# 4-20mA_Sensor.net
KiCad netlist of a schematic drawn in Altium Designer
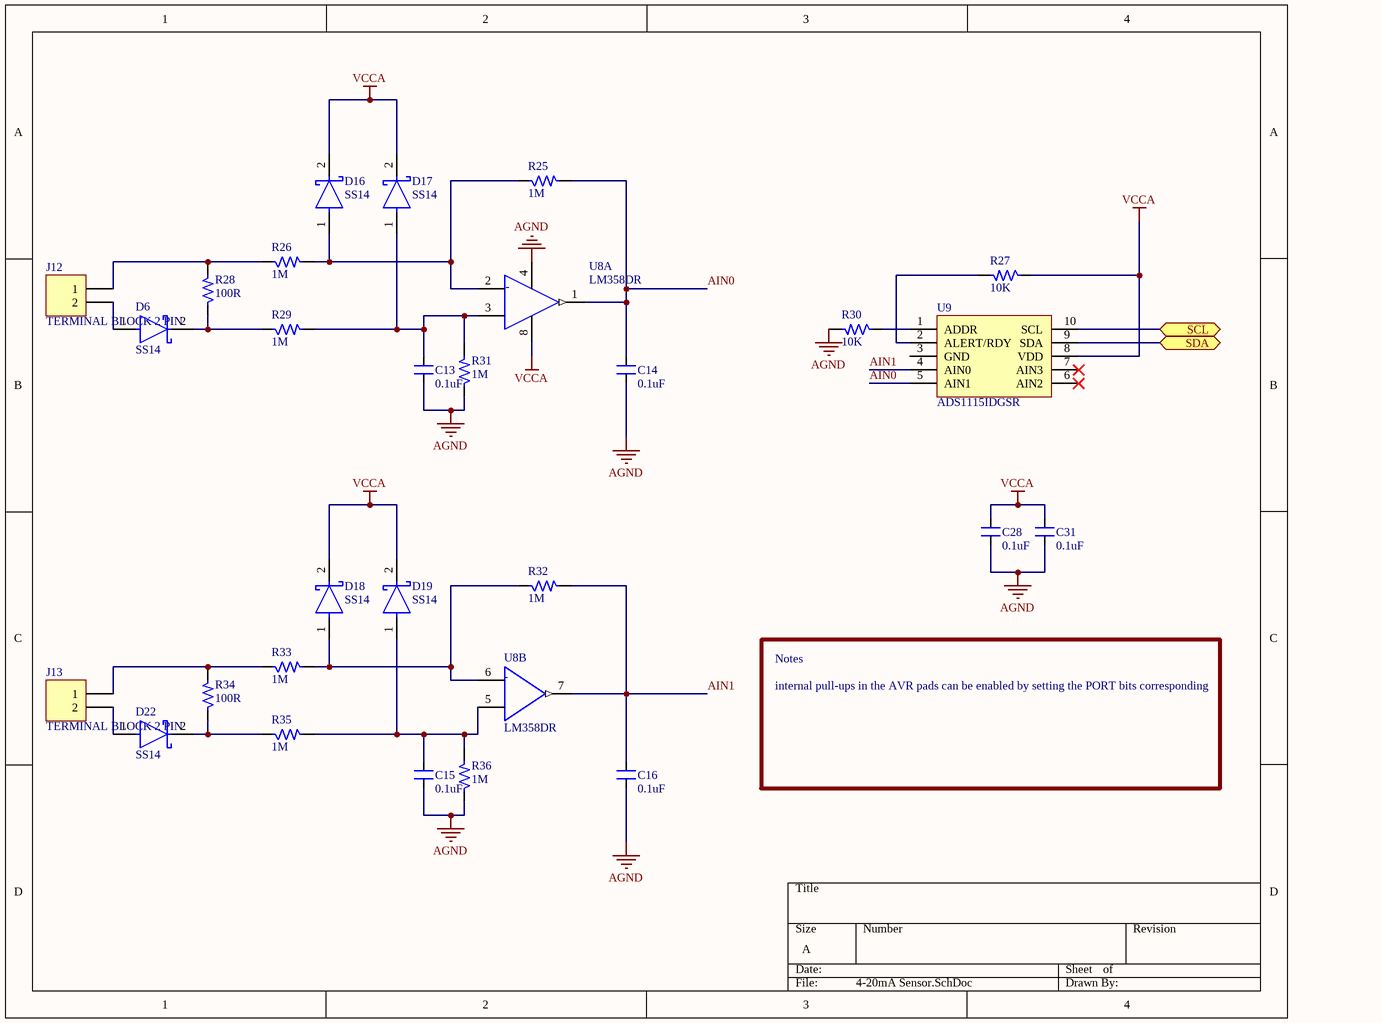
[diagram p0: 4-20mA Sensor.SchDoc]

(export (version "E")
  (design (tool "Eeschema 10.0.6"))
  (components
    (comp (ref "C13")
      (value "0.1uF")
      (footprint "CAP_0805")
      (description "0.1µF ±5% 50V Ceramic Capacitor X7R 0805 (2012 Metric)")
      (fields
        (field (name "MANUFACTURER") "AVX Corporation")
        (field (name "MANUFACTURER PART NUMBER") "08055C104JAT4A")
      )
      (libsource (lib "ESTEEMPCBLIB") (part "CAP_0.1uF-50V-5%-0805"))
    )
    (comp (ref "C14")
      (value "0.1uF")
      (footprint "CAP_0805")
      (description "0.1µF ±5% 50V Ceramic Capacitor X7R 0805 (2012 Metric)")
      (fields
        (field (name "MANUFACTURER") "AVX Corporation")
        (field (name "MANUFACTURER PART NUMBER") "08055C104JAT4A")
      )
      (libsource (lib "ESTEEMPCBLIB") (part "CAP_0.1uF-50V-5%-0805"))
    )
    (comp (ref "C15")
      (value "0.1uF")
      (footprint "CAP_0805")
      (description "0.1µF ±5% 50V Ceramic Capacitor X7R 0805 (2012 Metric)")
      (fields
        (field (name "MANUFACTURER") "AVX Corporation")
        (field (name "MANUFACTURER PART NUMBER") "08055C104JAT4A")
      )
      (libsource (lib "ESTEEMPCBLIB") (part "CAP_0.1uF-50V-5%-0805"))
    )
    (comp (ref "C16")
      (value "0.1uF")
      (footprint "CAP_0805")
      (description "0.1µF ±5% 50V Ceramic Capacitor X7R 0805 (2012 Metric)")
      (fields
        (field (name "MANUFACTURER") "AVX Corporation")
        (field (name "MANUFACTURER PART NUMBER") "08055C104JAT4A")
      )
      (libsource (lib "ESTEEMPCBLIB") (part "CAP_0.1uF-50V-5%-0805"))
    )
    (comp (ref "C28")
      (value "0.1uF")
      (footprint "CAP_0805")
      (description "0.1µF ±5% 50V Ceramic Capacitor X7R 0805 (2012 Metric)")
      (fields
        (field (name "MANUFACTURER") "AVX Corporation")
        (field (name "MANUFACTURER PART NUMBER") "08055C104JAT4A")
      )
      (libsource (lib "ESTEEMPCBLIB") (part "CAP_0.1uF-50V-5%-0805"))
    )
    (comp (ref "C31")
      (value "0.1uF")
      (footprint "CAP_0805")
      (description "0.1µF ±5% 50V Ceramic Capacitor X7R 0805 (2012 Metric)")
      (fields
        (field (name "MANUFACTURER") "AVX Corporation")
        (field (name "MANUFACTURER PART NUMBER") "08055C104JAT4A")
      )
      (libsource (lib "ESTEEMPCBLIB") (part "CAP_0.1uF-50V-5%-0805"))
    )
    (comp (ref "D6")
      (value "SS14")
      (footprint "FP-403AE-MFG")
      (description "DIODE SCHOTTKY 40V 1A SMA")
      (fields
        (field (name "MANUFACTURER") "ON Semiconductor")
        (field (name "OCTOPART") "https://octopart.com/ss14-on+semiconductor-29205033")
      )
      (libsource (lib "TAREKPCBLIB") (part "SS14"))
    )
    (comp (ref "D16")
      (value "SS14")
      (footprint "FP-403AE-MFG")
      (description "DIODE SCHOTTKY 40V 1A SMA")
      (fields
        (field (name "MANUFACTURER") "ON Semiconductor")
        (field (name "OCTOPART") "https://octopart.com/ss14-on+semiconductor-29205033")
      )
      (libsource (lib "TAREKPCBLIB") (part "SS14"))
    )
    (comp (ref "D17")
      (value "SS14")
      (footprint "FP-403AE-MFG")
      (description "DIODE SCHOTTKY 40V 1A SMA")
      (fields
        (field (name "MANUFACTURER") "ON Semiconductor")
        (field (name "OCTOPART") "https://octopart.com/ss14-on+semiconductor-29205033")
      )
      (libsource (lib "TAREKPCBLIB") (part "SS14"))
    )
    (comp (ref "D18")
      (value "SS14")
      (footprint "FP-403AE-MFG")
      (description "DIODE SCHOTTKY 40V 1A SMA")
      (fields
        (field (name "MANUFACTURER") "ON Semiconductor")
        (field (name "OCTOPART") "https://octopart.com/ss14-on+semiconductor-29205033")
      )
      (libsource (lib "TAREKPCBLIB") (part "SS14"))
    )
    (comp (ref "D19")
      (value "SS14")
      (footprint "FP-403AE-MFG")
      (description "DIODE SCHOTTKY 40V 1A SMA")
      (fields
        (field (name "MANUFACTURER") "ON Semiconductor")
        (field (name "OCTOPART") "https://octopart.com/ss14-on+semiconductor-29205033")
      )
      (libsource (lib "TAREKPCBLIB") (part "SS14"))
    )
    (comp (ref "D22")
      (value "SS14")
      (footprint "FP-403AE-MFG")
      (description "DIODE SCHOTTKY 40V 1A SMA")
      (fields
        (field (name "MANUFACTURER") "ON Semiconductor")
        (field (name "OCTOPART") "https://octopart.com/ss14-on+semiconductor-29205033")
      )
      (libsource (lib "TAREKPCBLIB") (part "SS14"))
    )
    (comp (ref "J12")
      (value "TERMINAL BLOCK 2 PIN")
      (footprint "CON2_P196_1729128_TH_ST")
      (description "2 Pins, 1 Row 5mm Pitch, straight Connector, male")
      (fields
        (field (name "MANUFACTURER") "Phoenix Contact")
        (field (name "MANUFACTURER PART NUMBER") "MKDSN1,5/2")
      )
      (libsource (lib "ESTEEMPCBLIB") (part "CON-TB_2X1-196-ST-TH"))
    )
    (comp (ref "J13")
      (value "TERMINAL BLOCK 2 PIN")
      (footprint "CON2_P196_1729128_TH_ST")
      (description "2 Pins, 1 Row 5mm Pitch, straight Connector, male")
      (fields
        (field (name "MANUFACTURER") "Phoenix Contact")
        (field (name "MANUFACTURER PART NUMBER") "MKDSN1,5/2")
      )
      (libsource (lib "ESTEEMPCBLIB") (part "CON-TB_2X1-196-ST-TH"))
    )
    (comp (ref "R25")
      (value "1M")
      (footprint "RES_0805")
      (description "1 MOhms ±1% 0.125W, 1/8W Chip Resistor 0805 (2012 Metric) Automotive AEC-Q200 Thick Film")
      (fields (field (name "MANUFACTURER") "Walsin") (field (name "MANUFACTURER PART NUMBER") "WR08X1004FTL"))
      (libsource (lib "ESTEEMPCBLIB") (part "RES_1M-0.125W-1%-0805"))
    )
    (comp (ref "R26")
      (value "1M")
      (footprint "RES_0805")
      (description "1 MOhms ±1% 0.125W, 1/8W Chip Resistor 0805 (2012 Metric) Automotive AEC-Q200 Thick Film")
      (fields (field (name "MANUFACTURER") "Walsin") (field (name "MANUFACTURER PART NUMBER") "WR08X1004FTL"))
      (libsource (lib "ESTEEMPCBLIB") (part "RES_1M-0.125W-1%-0805"))
    )
    (comp (ref "R27")
      (value "10K")
      (footprint "RES_0805")
      (description "10 kOhms ±1% 0.125W, 1/8W Chip Resistor 0805 (2012 Metric) Automotive AEC-Q200 Thick Film")
      (fields (field (name "MANUFACTURER") "CTS") (field (name "MANUFACTURER PART NUMBER") "WR08X1002FTL"))
      (libsource (lib "ESTEEMPCBLIB") (part "RES_10K-0.125W-1%-0805"))
    )
    (comp (ref "R28")
      (value "100R")
      (footprint "RES_0805")
      (fields (field (name "MANUFACTURER") "Walsin") (field (name "MANUFACTURER PART NUMBER") "WR08X1000FTL"))
      (libsource (lib "ESTEEMPCBLIB") (part "RES_100R-0.125W-1%-0805"))
    )
    (comp (ref "R29")
      (value "1M")
      (footprint "RES_0805")
      (description "1 MOhms ±1% 0.125W, 1/8W Chip Resistor 0805 (2012 Metric) Automotive AEC-Q200 Thick Film")
      (fields (field (name "MANUFACTURER") "Walsin") (field (name "MANUFACTURER PART NUMBER") "WR08X1004FTL"))
      (libsource (lib "ESTEEMPCBLIB") (part "RES_1M-0.125W-1%-0805"))
    )
    (comp (ref "R30")
      (value "10K")
      (footprint "RES_0805")
      (description "10 kOhms ±1% 0.125W, 1/8W Chip Resistor 0805 (2012 Metric) Automotive AEC-Q200 Thick Film")
      (fields (field (name "MANUFACTURER") "CTS") (field (name "MANUFACTURER PART NUMBER") "WR08X1002FTL"))
      (libsource (lib "ESTEEMPCBLIB") (part "RES_10K-0.125W-1%-0805"))
    )
    (comp (ref "R31")
      (value "1M")
      (footprint "RES_0805")
      (description "1 MOhms ±1% 0.125W, 1/8W Chip Resistor 0805 (2012 Metric) Automotive AEC-Q200 Thick Film")
      (fields (field (name "MANUFACTURER") "Walsin") (field (name "MANUFACTURER PART NUMBER") "WR08X1004FTL"))
      (libsource (lib "ESTEEMPCBLIB") (part "RES_1M-0.125W-1%-0805"))
    )
    (comp (ref "R32")
      (value "1M")
      (footprint "RES_0805")
      (description "1 MOhms ±1% 0.125W, 1/8W Chip Resistor 0805 (2012 Metric) Automotive AEC-Q200 Thick Film")
      (fields (field (name "MANUFACTURER") "Walsin") (field (name "MANUFACTURER PART NUMBER") "WR08X1004FTL"))
      (libsource (lib "ESTEEMPCBLIB") (part "RES_1M-0.125W-1%-0805"))
    )
    (comp (ref "R33")
      (value "1M")
      (footprint "RES_0805")
      (description "1 MOhms ±1% 0.125W, 1/8W Chip Resistor 0805 (2012 Metric) Automotive AEC-Q200 Thick Film")
      (fields (field (name "MANUFACTURER") "Walsin") (field (name "MANUFACTURER PART NUMBER") "WR08X1004FTL"))
      (libsource (lib "ESTEEMPCBLIB") (part "RES_1M-0.125W-1%-0805"))
    )
    (comp (ref "R34")
      (value "100R")
      (footprint "RES_0805")
      (fields (field (name "MANUFACTURER") "Walsin") (field (name "MANUFACTURER PART NUMBER") "WR08X1000FTL"))
      (libsource (lib "ESTEEMPCBLIB") (part "RES_100R-0.125W-1%-0805"))
    )
    (comp (ref "R35")
      (value "1M")
      (footprint "RES_0805")
      (description "1 MOhms ±1% 0.125W, 1/8W Chip Resistor 0805 (2012 Metric) Automotive AEC-Q200 Thick Film")
      (fields (field (name "MANUFACTURER") "Walsin") (field (name "MANUFACTURER PART NUMBER") "WR08X1004FTL"))
      (libsource (lib "ESTEEMPCBLIB") (part "RES_1M-0.125W-1%-0805"))
    )
    (comp (ref "R36")
      (value "1M")
      (footprint "RES_0805")
      (description "1 MOhms ±1% 0.125W, 1/8W Chip Resistor 0805 (2012 Metric) Automotive AEC-Q200 Thick Film")
      (fields (field (name "MANUFACTURER") "Walsin") (field (name "MANUFACTURER PART NUMBER") "WR08X1004FTL"))
      (libsource (lib "ESTEEMPCBLIB") (part "RES_1M-0.125W-1%-0805"))
    )
    (comp (ref "U8")
      (value "LM358DR")
      (footprint "FP-D0008A-IPC_B")
      (description "IC OPAMP GP 2 CIRCUIT 8SOIC")
      (libsource (lib "TAREKPCBLIB") (part "LM358"))
    )
    (comp (ref "U9")
      (value "ADS1115IDGSR")
      (footprint "VSOP-10_19.6_230_57X12_SMD")
      (description "Analog to Digital Converters - ADC 16B ADC w/ Int MUX PGA Comp Osc & Ref")
      (fields (field (name "MANUFACTURER") "Texas Instruments"))
      (libsource (lib "ESTEEMPCBLIB") (part "IC_ADS1115IDGSR"))
    )
  )
  (nets
    (net (code "1") (name "/AIN0") (class "Default")
      (node (ref "C14") (pin "2") (pinfunction "2_2") (pintype "passive"))
      (node (ref "R25") (pin "2") (pinfunction "2_2") (pintype "passive"))
      (node (ref "U8") (pin "1") (pinfunction "1OUT_1") (pintype "output"))
      (node (ref "U9") (pin "5") (pinfunction "AIN1_5") (pintype "passive"))
    )
    (net (code "2") (name "/AIN1") (class "Default")
      (node (ref "C16") (pin "2") (pinfunction "2_2") (pintype "passive"))
      (node (ref "R32") (pin "2") (pinfunction "2_2") (pintype "passive"))
      (node (ref "U8") (pin "7") (pinfunction "2OUT_7") (pintype "output"))
      (node (ref "U9") (pin "4") (pinfunction "AIN0_4") (pintype "passive"))
    )
    (net (code "3") (name "/SCL") (class "Default")
      (node (ref "U9") (pin "10") (pinfunction "SCL_10") (pintype "passive"))
    )
    (net (code "4") (name "/SDA") (class "Default")
      (node (ref "U9") (pin "9") (pinfunction "SDA_9") (pintype "passive"))
    )
    (net (code "5") (name "AGND") (class "Default")
      (node (ref "C13") (pin "1") (pinfunction "1_1") (pintype "passive"))
      (node (ref "C14") (pin "1") (pinfunction "1_1") (pintype "passive"))
      (node (ref "C15") (pin "1") (pinfunction "1_1") (pintype "passive"))
      (node (ref "C16") (pin "1") (pinfunction "1_1") (pintype "passive"))
      (node (ref "C28") (pin "1") (pinfunction "1_1") (pintype "passive"))
      (node (ref "C31") (pin "1") (pinfunction "1_1") (pintype "passive"))
      (node (ref "R30") (pin "2") (pinfunction "2_2") (pintype "passive"))
      (node (ref "R31") (pin "1") (pinfunction "1_1") (pintype "passive"))
      (node (ref "R36") (pin "1") (pinfunction "1_1") (pintype "passive"))
      (node (ref "U8") (pin "4") (pinfunction "V-_4") (pintype "power_in"))
    )
    (net (code "6") (name "Net-(D6-A)") (class "Default")
      (node (ref "D6") (pin "1") (pinfunction "A_1") (pintype "passive"))
      (node (ref "J12") (pin "2") (pinfunction "2_2") (pintype "passive"))
    )
    (net (code "7") (name "Net-(D6-C)") (class "Default")
      (node (ref "D6") (pin "2") (pinfunction "C_2") (pintype "passive"))
      (node (ref "R28") (pin "1") (pinfunction "1_1") (pintype "passive"))
      (node (ref "R29") (pin "1") (pinfunction "1_1") (pintype "passive"))
    )
    (net (code "8") (name "Net-(D16-A)") (class "Default")
      (node (ref "D16") (pin "1") (pinfunction "A_1") (pintype "passive"))
      (node (ref "R25") (pin "1") (pinfunction "1_1") (pintype "passive"))
      (node (ref "R26") (pin "2") (pinfunction "2_2") (pintype "passive"))
      (node (ref "U8") (pin "2") (pinfunction "IN1-_2") (pintype "tri_state"))
    )
    (net (code "9") (name "Net-(D17-A)") (class "Default")
      (node (ref "C13") (pin "2") (pinfunction "2_2") (pintype "passive"))
      (node (ref "D17") (pin "1") (pinfunction "A_1") (pintype "passive"))
      (node (ref "R29") (pin "2") (pinfunction "2_2") (pintype "passive"))
      (node (ref "R31") (pin "2") (pinfunction "2_2") (pintype "passive"))
      (node (ref "U8") (pin "3") (pinfunction "IN1+_3") (pintype "tri_state"))
    )
    (net (code "10") (name "Net-(D18-A)") (class "Default")
      (node (ref "D18") (pin "1") (pinfunction "A_1") (pintype "passive"))
      (node (ref "R32") (pin "1") (pinfunction "1_1") (pintype "passive"))
      (node (ref "R33") (pin "2") (pinfunction "2_2") (pintype "passive"))
      (node (ref "U8") (pin "6") (pinfunction "IN2-_6") (pintype "tri_state"))
    )
    (net (code "11") (name "Net-(D19-A)") (class "Default")
      (node (ref "C15") (pin "2") (pinfunction "2_2") (pintype "passive"))
      (node (ref "D19") (pin "1") (pinfunction "A_1") (pintype "passive"))
      (node (ref "R35") (pin "2") (pinfunction "2_2") (pintype "passive"))
      (node (ref "R36") (pin "2") (pinfunction "2_2") (pintype "passive"))
      (node (ref "U8") (pin "5") (pinfunction "IN2+_5") (pintype "tri_state"))
    )
    (net (code "12") (name "Net-(D22-A)") (class "Default")
      (node (ref "D22") (pin "1") (pinfunction "A_1") (pintype "passive"))
      (node (ref "J13") (pin "2") (pinfunction "2_2") (pintype "passive"))
    )
    (net (code "13") (name "Net-(D22-C)") (class "Default")
      (node (ref "D22") (pin "2") (pinfunction "C_2") (pintype "passive"))
      (node (ref "R34") (pin "1") (pinfunction "1_1") (pintype "passive"))
      (node (ref "R35") (pin "1") (pinfunction "1_1") (pintype "passive"))
    )
    (net (code "14") (name "Net-(J12-Pad1)") (class "Default")
      (node (ref "J12") (pin "1") (pinfunction "1_1") (pintype "passive"))
      (node (ref "R26") (pin "1") (pinfunction "1_1") (pintype "passive"))
      (node (ref "R28") (pin "2") (pinfunction "2_2") (pintype "passive"))
    )
    (net (code "15") (name "Net-(J13-Pad1)") (class "Default")
      (node (ref "J13") (pin "1") (pinfunction "1_1") (pintype "passive"))
      (node (ref "R33") (pin "1") (pinfunction "1_1") (pintype "passive"))
      (node (ref "R34") (pin "2") (pinfunction "2_2") (pintype "passive"))
    )
    (net (code "16") (name "Net-(U9-ADDR)") (class "Default")
      (node (ref "R30") (pin "1") (pinfunction "1_1") (pintype "passive"))
      (node (ref "U9") (pin "1") (pinfunction "ADDR_1") (pintype "passive"))
    )
    (net (code "17") (name "Net-(U9-ALERT{slash}RDY)") (class "Default")
      (node (ref "R27") (pin "2") (pinfunction "2_2") (pintype "passive"))
      (node (ref "U9") (pin "2") (pinfunction "ALERT/RDY_2") (pintype "passive"))
    )
    (net (code "18") (name "VCCA") (class "Default")
      (node (ref "C28") (pin "2") (pinfunction "2_2") (pintype "passive"))
      (node (ref "C31") (pin "2") (pinfunction "2_2") (pintype "passive"))
      (node (ref "D16") (pin "2") (pinfunction "C_2") (pintype "passive"))
      (node (ref "D17") (pin "2") (pinfunction "C_2") (pintype "passive"))
      (node (ref "D18") (pin "2") (pinfunction "C_2") (pintype "passive"))
      (node (ref "D19") (pin "2") (pinfunction "C_2") (pintype "passive"))
      (node (ref "R27") (pin "1") (pinfunction "1_1") (pintype "passive"))
      (node (ref "U8") (pin "8") (pinfunction "V+_8") (pintype "power_in"))
      (node (ref "U9") (pin "8") (pinfunction "VDD_8") (pintype "passive"))
    )
    (net (code "19") (name "unconnected-(U9-AIN2-Pad6)") (class "Default")
      (node (ref "U9") (pin "6") (pinfunction "AIN2_6") (pintype "passive+no_connect"))
    )
    (net (code "20") (name "unconnected-(U9-AIN3-Pad7)") (class "Default")
      (node (ref "U9") (pin "7") (pinfunction "AIN3_7") (pintype "passive+no_connect"))
    )
    (net (code "21") (name "unconnected-(U9-GND-Pad3)") (class "Default")
      (node (ref "U9") (pin "3") (pinfunction "GND_3") (pintype "passive"))
    )
  )
)
